# voltage_adjustable_supply.net
KiCad netlist of a schematic drawn in Altium Designer
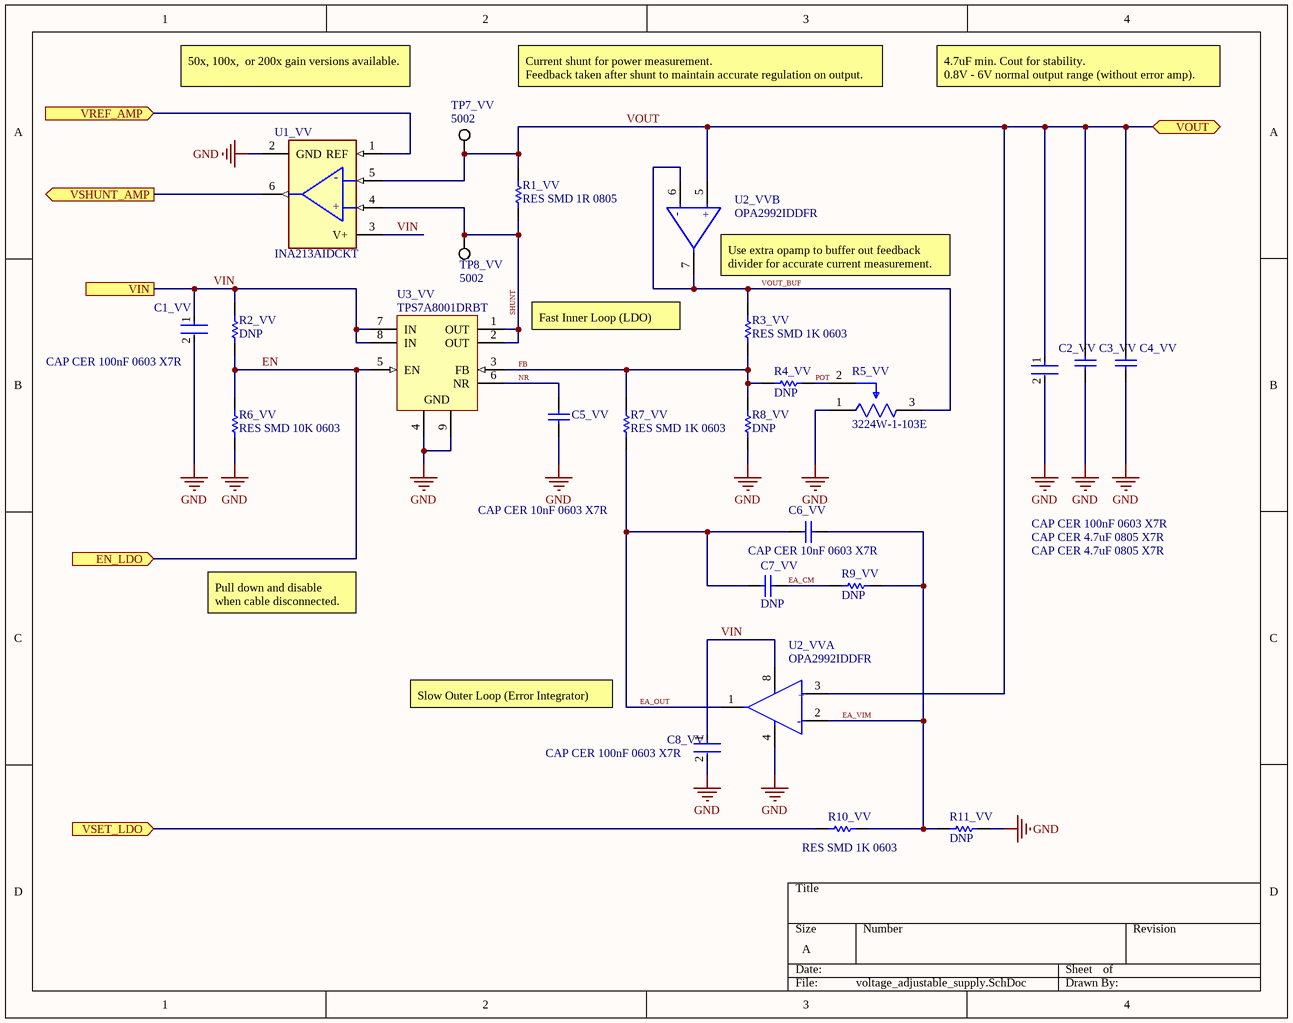
[diagram p0: voltage_adjustable_supply.SchDoc]

(export (version "E")
  (design (tool "Eeschema 10.0.6"))
  (components
    (comp (ref "C1_VV")
      (value "CAP CER 100nF 0603 X7R")
      (footprint "FP-CC0603-DA-MFG")
      (description "CAP CER 0.1UF 16V X7R 0603")
      (fields
        (field (name "OCTOPART") "https://octopart.com/cc0603krx7r7bb104-yageo-192941")
        (field (name "TOLERANCE") "0.1")
      )
      (libsource (lib "Altium Content Vault") (part "11868f565c42a9108669ba33697ecf6"))
    )
    (comp (ref "C2_VV")
      (value "CAP CER 100nF 0603 X7R")
      (footprint "FP-CC0603-DA-MFG")
      (description "CAP CER 0.1UF 16V X7R 0603")
      (fields
        (field (name "OCTOPART") "https://octopart.com/cc0603krx7r7bb104-yageo-192941")
        (field (name "TOLERANCE") "0.1")
      )
      (libsource (lib "Altium Content Vault") (part "11868f565c42a9108669ba33697ecf6"))
    )
    (comp (ref "C3_VV")
      (value "CAP CER 4.7uF 0805 X7R")
      (footprint "CAPC2013X140X50NL20T25")
      (fields
        (field (name "PART NUMBER") "0805ZC475KAT2A")
        (field (name "MANUFACTURER") "AVX Interconnect / Elco")
      )
      (libsource (lib "Altium Content Vault") (part "CAP"))
    )
    (comp (ref "C4_VV")
      (value "CAP CER 4.7uF 0805 X7R")
      (footprint "CAPC2013X140X50NL20T25")
      (fields
        (field (name "PART NUMBER") "0805ZC475KAT2A")
        (field (name "MANUFACTURER") "AVX Interconnect / Elco")
      )
      (libsource (lib "Altium Content Vault") (part "CAP"))
    )
    (comp (ref "C5_VV")
      (value "CAP CER 10nF 0603 X7R")
      (footprint "CAPC1608X90X40ML10T20")
      (description "Chip Capacitor, 10 nF, +/- 10%, 50 V, -55 to 125 degC, 0603 (1608 Metric), RoHS, Tape and Reel")
      (fields (field (name "MANUFACTURER") "Yageo") (field (name "TOLERANCE") "10%"))
      (libsource (lib "Altium Content Vault") (part "CAP-NP-2"))
    )
    (comp (ref "C6_VV")
      (value "CAP CER 10nF 0603 X7R")
      (footprint "CAPC1608X90X40ML10T20")
      (description "Chip Capacitor, 10 nF, +/- 10%, 50 V, -55 to 125 degC, 0603 (1608 Metric), RoHS, Tape and Reel")
      (fields (field (name "MANUFACTURER") "Yageo") (field (name "TOLERANCE") "10%"))
      (libsource (lib "Altium Content Vault") (part "CAP-NP-2"))
    )
    (comp (ref "C7_VV")
      (value "DNP")
      (footprint "CAPC1608X90X40ML10T20")
      (description "Chip Capacitor, 10 nF, +/- 10%, 50 V, -55 to 125 degC, 0603 (1608 Metric), RoHS, Tape and Reel")
      (fields (field (name "MANUFACTURER") "Yageo") (field (name "TOLERANCE") "10%"))
      (libsource (lib "Altium Content Vault") (part "CAP-NP-2"))
    )
    (comp (ref "C8_VV")
      (value "CAP CER 100nF 0603 X7R")
      (footprint "FP-CC0603-DA-MFG")
      (description "CAP CER 0.1UF 16V X7R 0603")
      (fields
        (field (name "OCTOPART") "https://octopart.com/cc0603krx7r7bb104-yageo-192941")
        (field (name "TOLERANCE") "0.1")
      )
      (libsource (lib "Altium Content Vault") (part "11868f565c42a9108669ba33697ecf6"))
    )
    (comp (ref "R1_VV")
      (value "RES SMD 1R 0805")
      (footprint "RESC2013X50X30NL20T20")
      (fields (field (name "MANUFACTURER") "Vishay Dale") (field (name "PART NUMBER") "CRCW08050000Z0EB"))
      (libsource (lib "Altium Content Vault") (part "RES"))
    )
    (comp (ref "R2_VV")
      (value "DNP")
      (footprint "RESC1609X50X30LL10T20")
      (fields (field (name "PART NUMBER") "CRCW0603100KFKEA") (field (name "MANUFACTURER") "Vishay Dale"))
      (libsource (lib "Altium Content Vault") (part "RES"))
    )
    (comp (ref "R3_VV")
      (value "RES SMD 1K 0603")
      (footprint "RESC1609X50X30LL10T20")
      (description "DNP")
      (fields (field (name "PART NUMBER") "CRCW0603100KFKEA") (field (name "MANUFACTURER") "Vishay Dale"))
      (libsource (lib "Altium Content Vault") (part "RES"))
    )
    (comp (ref "R4_VV")
      (value "DNP")
      (footprint "RESC1609X50X30LL10T20")
      (fields (field (name "PART NUMBER") "CRCW0603100KFKEA") (field (name "MANUFACTURER") "Vishay Dale"))
      (libsource (lib "Altium Content Vault") (part "RES"))
    )
    (comp (ref "R5_VV")
      (value "3224W-1-103E")
      (footprint "FP-3224W-MFG")
      (description "TRIMMER 10K OHM 0.25W J LEAD TOP")
      (fields (field (name "TOLERANCE") "10%") (field (name "MANUFACTURER") "Bourns"))
      (libsource (lib "Altium Content Vault") (part "83d3d349ed884d1db45cec512f27eb6"))
    )
    (comp (ref "R6_VV")
      (value "RES SMD 10K 0603")
      (footprint "RESC1609X50X30LL10T20")
      (description "DNP")
      (fields (field (name "PART NUMBER") "CRCW0603100KFKEA") (field (name "MANUFACTURER") "Vishay Dale"))
      (libsource (lib "Altium Content Vault") (part "RES"))
    )
    (comp (ref "R7_VV")
      (value "RES SMD 1K 0603")
      (footprint "RESC1609X50X30LL10T20")
      (description "DNP")
      (fields (field (name "PART NUMBER") "CRCW0603100KFKEA") (field (name "MANUFACTURER") "Vishay Dale"))
      (libsource (lib "Altium Content Vault") (part "RES"))
    )
    (comp (ref "R8_VV")
      (value "DNP")
      (footprint "RESC1609X50X30LL10T20")
      (fields (field (name "PART NUMBER") "CRCW0603100KFKEA") (field (name "MANUFACTURER") "Vishay Dale"))
      (libsource (lib "Altium Content Vault") (part "RES"))
    )
    (comp (ref "R9_VV")
      (value "DNP")
      (footprint "RESC1609X50X30LL10T20")
      (fields (field (name "PART NUMBER") "CRCW0603100KFKEA") (field (name "MANUFACTURER") "Vishay Dale"))
      (libsource (lib "Altium Content Vault") (part "RES"))
    )
    (comp (ref "R10_VV")
      (value "RES SMD 1K 0603")
      (footprint "RESC1609X50X30LL10T20")
      (description "DNP")
      (fields (field (name "PART NUMBER") "CRCW0603100KFKEA") (field (name "MANUFACTURER") "Vishay Dale"))
      (libsource (lib "Altium Content Vault") (part "RES"))
    )
    (comp (ref "R11_VV")
      (value "DNP")
      (footprint "RESC1609X50X30LL10T20")
      (fields (field (name "PART NUMBER") "CRCW0603100KFKEA") (field (name "MANUFACTURER") "Vishay Dale"))
      (libsource (lib "Altium Content Vault") (part "RES"))
    )
    (comp (ref "TP7_VV")
      (value "5002")
      (footprint "KSTN-5002")
      (description "Test Point, White, 1-Pin THD, RoHS, Bulk")
      (fields (field (name "MANUFACTURER") "KeystoneElectronics"))
      (libsource (lib "Altium Content Vault") (part "KSTN-TP-5002"))
    )
    (comp (ref "TP8_VV")
      (value "5002")
      (footprint "KSTN-5002")
      (description "Test Point, White, 1-Pin THD, RoHS, Bulk")
      (fields (field (name "MANUFACTURER") "KeystoneElectronics"))
      (libsource (lib "Altium Content Vault") (part "KSTN-TP-5002"))
    )
    (comp (ref "U1_VV")
      (value "INA213AIDCKT")
      (footprint "FP-DCK0006A-MFG")
      (description "IC CURR SENSE 1 CIRCUIT SC70-6")
      (fields
        (field (name "MANUFACTURER") "Texas Instruments")
        (field (name "OCTOPART") "https://octopart.com/ina213aidckt-texas+instruments-7767892")
      )
      (libsource (lib "Altium Content Vault") (part "9e0f38de031fe9615e73145e91d432c"))
    )
    (comp (ref "U2_VV")
      (value "OPA2992IDDFR")
      (footprint "FP-DDF0008A-MFG")
      (description "IC OPAMP GP 2 CIRCUIT TSOT23-8")
      (libsource (lib "Altium Content Vault") (part "d5b36c1049528187b1d2197d5d58d7e"))
    )
    (comp (ref "U3_VV")
      (value "TPS7A8001DRBT")
      (footprint "DRB0008A_V")
      (fields (field (name "MANUFACTURER") "Texas Instruments"))
      (libsource (lib "Altium Content Vault") (part "TI-TPS7A8X01DRB8-1750X1500TP"))
    )
  )
  (nets
    (net (code "1") (name "/EA_CM") (class "Default")
      (node (ref "C7_VV") (pin "2") (pinfunction "2_2") (pintype "passive"))
      (node (ref "R9_VV") (pin "2") (pinfunction "2_2") (pintype "passive"))
    )
    (net (code "2") (name "/EA_OUT") (class "Default")
      (node (ref "C6_VV") (pin "1") (pinfunction "1_1") (pintype "passive"))
      (node (ref "C7_VV") (pin "1") (pinfunction "1_1") (pintype "passive"))
      (node (ref "R7_VV") (pin "1") (pinfunction "1_1") (pintype "passive"))
      (node (ref "U2_VV") (pin "1") (pinfunction "OUT1_1") (pintype "passive"))
    )
    (net (code "3") (name "/EA_VIM") (class "Default")
      (node (ref "C6_VV") (pin "2") (pinfunction "2_2") (pintype "passive"))
      (node (ref "R10_VV") (pin "1") (pinfunction "1_1") (pintype "passive"))
      (node (ref "R11_VV") (pin "2") (pinfunction "2_2") (pintype "passive"))
      (node (ref "R9_VV") (pin "1") (pinfunction "1_1") (pintype "passive"))
      (node (ref "U2_VV") (pin "2") (pinfunction "IN1-_2") (pintype "tri_state"))
    )
    (net (code "4") (name "/EN") (class "Default")
      (node (ref "R2_VV") (pin "1") (pinfunction "1_1") (pintype "passive"))
      (node (ref "R6_VV") (pin "2") (pinfunction "2_2") (pintype "passive"))
      (node (ref "U3_VV") (pin "5") (pinfunction "EN_5") (pintype "input"))
    )
    (net (code "5") (name "/FB") (class "Default")
      (node (ref "R3_VV") (pin "1") (pinfunction "1_1") (pintype "passive"))
      (node (ref "R4_VV") (pin "2") (pinfunction "2_2") (pintype "passive"))
      (node (ref "R7_VV") (pin "2") (pinfunction "2_2") (pintype "passive"))
      (node (ref "R8_VV") (pin "2") (pinfunction "2_2") (pintype "passive"))
      (node (ref "U3_VV") (pin "3") (pinfunction "FB_3") (pintype "input"))
    )
    (net (code "6") (name "/NR") (class "Default")
      (node (ref "C5_VV") (pin "1") (pinfunction "1_1") (pintype "passive"))
      (node (ref "U3_VV") (pin "6") (pinfunction "NR_6") (pintype "passive"))
    )
    (net (code "7") (name "/POT") (class "Default")
      (node (ref "R4_VV") (pin "1") (pinfunction "1_1") (pintype "passive"))
      (node (ref "R5_VV") (pin "2") (pinfunction "WIPER_2") (pintype "passive"))
    )
    (net (code "8") (name "/SHUNT") (class "Default")
      (node (ref "R1_VV") (pin "1") (pinfunction "1_1") (pintype "passive"))
      (node (ref "TP8_VV") (pin "1") (pintype "passive"))
      (node (ref "U1_VV") (pin "4") (pinfunction "IN+_4") (pintype "input"))
      (node (ref "U3_VV") (pin "1") (pinfunction "OUT_1") (pintype "power_in"))
      (node (ref "U3_VV") (pin "2") (pinfunction "OUT_2") (pintype "power_in"))
    )
    (net (code "9") (name "/VIN") (class "Default")
      (node (ref "C1_VV") (pin "1") (pinfunction "1_1") (pintype "passive"))
      (node (ref "C8_VV") (pin "1") (pinfunction "1_1") (pintype "passive"))
      (node (ref "R2_VV") (pin "2") (pinfunction "2_2") (pintype "passive"))
      (node (ref "U1_VV") (pin "3") (pinfunction "V+_3") (pintype "power_in"))
      (node (ref "U2_VV") (pin "8") (pinfunction "V+_8") (pintype "power_in"))
      (node (ref "U3_VV") (pin "7") (pinfunction "IN_7") (pintype "power_in"))
      (node (ref "U3_VV") (pin "8") (pinfunction "IN_8") (pintype "power_in"))
    )
    (net (code "10") (name "/VOUT") (class "Default")
      (node (ref "C2_VV") (pin "1") (pinfunction "1_1") (pintype "passive"))
      (node (ref "C3_VV") (pin "1") (pinfunction "1_1") (pintype "passive"))
      (node (ref "C4_VV") (pin "1") (pinfunction "1_1") (pintype "passive"))
      (node (ref "R1_VV") (pin "2") (pinfunction "2_2") (pintype "passive"))
      (node (ref "TP7_VV") (pin "1") (pintype "passive"))
      (node (ref "U1_VV") (pin "5") (pinfunction "IN-_5") (pintype "input"))
      (node (ref "U2_VV") (pin "3") (pinfunction "IN1+_3") (pintype "tri_state"))
      (node (ref "U2_VV") (pin "5") (pinfunction "IN2+_5") (pintype "tri_state"))
    )
    (net (code "11") (name "/VOUT_BUF") (class "Default")
      (node (ref "R3_VV") (pin "2") (pinfunction "2_2") (pintype "passive"))
      (node (ref "R5_VV") (pin "3") (pinfunction "CW_3") (pintype "passive"))
      (node (ref "U2_VV") (pin "6") (pinfunction "IN2-_6") (pintype "tri_state"))
      (node (ref "U2_VV") (pin "7") (pinfunction "OUT2_7") (pintype "passive"))
    )
    (net (code "12") (name "/VREF_AMP") (class "Default")
      (node (ref "U1_VV") (pin "1") (pinfunction "REF_1") (pintype "input"))
    )
    (net (code "13") (name "/VSET_LDO") (class "Default")
      (node (ref "R10_VV") (pin "2") (pinfunction "2_2") (pintype "passive"))
    )
    (net (code "14") (name "/VSHUNT_AMP") (class "Default")
      (node (ref "U1_VV") (pin "6") (pinfunction "OUT_6") (pintype "output"))
    )
    (net (code "15") (name "GND") (class "Default")
      (node (ref "C1_VV") (pin "2") (pinfunction "2_2") (pintype "passive"))
      (node (ref "C2_VV") (pin "2") (pinfunction "2_2") (pintype "passive"))
      (node (ref "C3_VV") (pin "2") (pinfunction "2_2") (pintype "passive"))
      (node (ref "C4_VV") (pin "2") (pinfunction "2_2") (pintype "passive"))
      (node (ref "C5_VV") (pin "2") (pinfunction "2_2") (pintype "passive"))
      (node (ref "C8_VV") (pin "2") (pinfunction "2_2") (pintype "passive"))
      (node (ref "R11_VV") (pin "1") (pinfunction "1_1") (pintype "passive"))
      (node (ref "R5_VV") (pin "1") (pinfunction "CCW_1") (pintype "passive"))
      (node (ref "R6_VV") (pin "1") (pinfunction "1_1") (pintype "passive"))
      (node (ref "R8_VV") (pin "1") (pinfunction "1_1") (pintype "passive"))
      (node (ref "U1_VV") (pin "2") (pinfunction "GND_2") (pintype "power_in"))
      (node (ref "U2_VV") (pin "4") (pinfunction "V-_4") (pintype "power_in"))
      (node (ref "U3_VV") (pin "4") (pinfunction "GND_4") (pintype "power_in"))
      (node (ref "U3_VV") (pin "9") (pinfunction "GND_9") (pintype "power_in"))
    )
  )
)
